# Audio-Module-SCH.net
KiCad netlist of a schematic drawn in Altium Designer
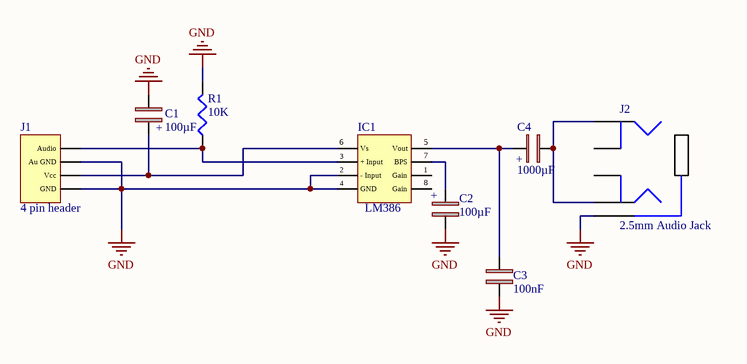
[diagram p0: Audio-Module-SCH.SchDoc]

(export (version "E")
  (design (tool "Eeschema 10.0.6"))
  (components
    (comp (ref "C1")
      (value "100µF")
      (footprint "ELCO")
      (description "CAP ALUM 100UF 20% 10V SMD")
      (fields
        (field (name "MANUFACTURER") "Panasonic")
        (field (name "MANUFACTURER PART NUMBER") "EEE-1AA101WR")
      )
      (libsource (lib "Audio-Module-SCH-LIB") (part "Capacitor{colon} 100µF (elco)"))
    )
    (comp (ref "C2")
      (value "100µF")
      (footprint "ELCO")
      (description "CAP ALUM 100UF 20% 10V SMD")
      (fields
        (field (name "MANUFACTURER") "Panasonic")
        (field (name "MANUFACTURER PART NUMBER") "EEE-1AA101WR")
      )
      (libsource (lib "") (part "Capacitor{colon} 100µF (elco)_1"))
    )
    (comp (ref "C3")
      (value "100nF")
      (footprint "CAPACITOR 1206")
      (description "Ceramic capacitor SMD-1206 100nF /50V X7R# K +-10%, AVX, RoHS, /4000 reel/")
      (fields
        (field (name "MANUFACTURER") "Kyocera AVX")
        (field (name "MANUFACTURER PART NUMBER") "12065C104KAT2A")
      )
      (libsource (lib "Audio-Module-SCH-LIB") (part "Capacitor{colon} 100nF"))
    )
    (comp (ref "C4")
      (value "1000µF")
      (footprint "ELCO")
      (description "Capacitor; Aluminum Electrolytic; Ecap 1000uF 25V H13 Case FK SMT")
      (fields
        (field (name "MANUFACTURER") "Panasonic")
        (field (name "MANUFACTURER PART NUMBER") "EEE-FK1E102AQ")
      )
      (libsource (lib "Audio-Module-SCH-LIB") (part "Capacitor{colon} 1000µF (elco)"))
    )
    (comp (ref "IC1")
      (value "LM386")
      (footprint "LM386 SOP8")
      (description "Audio Amplifier, 0.325W, 1 Chann")
      (fields
        (field (name "MANUFACTURER") "TI National Semiconductor")
        (field (name "MANUFACTURER PART NUMBER") "LM386M-1")
      )
      (libsource (lib "Audio-Module-SCH-LIB") (part "IC{colon} LM386"))
    )
    (comp (ref "J1")
      (value "4 pin header")
      (footprint "4 HDR")
      (description "Male 4 pin header")
      (libsource (lib "Audio-Module-SCH-LIB") (part "CONNECTOR{colon} 4 pin header"))
    )
    (comp (ref "J2")
      (value "2.5mm Audio Jack")
      (footprint "AUDIO JACK")
      (description "Conn Audio RCP 6 POS Solder RA SMD 6 Terminal 1 Port T/R")
      (fields
        (field (name "MANUFACTURER") "Kycon")
        (field (name "MANUFACTURER PART NUMBER") "STX-25427-6N-TR")
      )
      (libsource (lib "Audio-Module-SCH-LIB") (part "Connector{colon} Audio Jack"))
    )
    (comp (ref "R1")
      (value "10K")
      (footprint "RESISTOR 0805")
      (description "Res Thick Film 0805 10K Ohm 5% 1/8W ±200ppm/°C Molded SMD SMD Paper T/R")
      (fields
        (field (name "MANUFACTURER") "Vishay Dale")
        (field (name "MANUFACTURER PART NUMBER") "CRCW080510K0JNEB")
      )
      (libsource (lib "Audio-Module-SCH-LIB") (part "Resistor{colon} 10K R"))
    )
  )
  (nets
    (net (code "1") (name "GND") (class "Default")
      (node (ref "C1") (pin "2") (pinfunction "-_2") (pintype "passive"))
      (node (ref "C2") (pin "2") (pinfunction "-_2") (pintype "passive"))
      (node (ref "C3") (pin "2") (pinfunction "2_2") (pintype "passive"))
      (node (ref "IC1") (pin "2") (pinfunction "-_Input_2") (pintype "passive"))
      (node (ref "IC1") (pin "4") (pinfunction "GND_4") (pintype "passive"))
      (node (ref "J1") (pin "1") (pinfunction "GND_1") (pintype "passive"))
      (node (ref "J1") (pin "3") (pinfunction "Au_GND_3") (pintype "passive"))
      (node (ref "J2") (pin "5") (pinfunction "Sleeve_5") (pintype "passive"))
      (node (ref "R1") (pin "2") (pinfunction "2_2") (pintype "passive"))
    )
    (net (code "2") (name "Net-(C1-+)") (class "Default")
      (node (ref "C1") (pin "1") (pinfunction "+_1") (pintype "passive"))
      (node (ref "IC1") (pin "6") (pinfunction "Vs_6") (pintype "passive"))
      (node (ref "J1") (pin "2") (pinfunction "Vcc_2") (pintype "passive"))
    )
    (net (code "3") (name "Net-(C2-+)") (class "Default")
      (node (ref "C2") (pin "1") (pinfunction "+_1") (pintype "passive"))
      (node (ref "IC1") (pin "7") (pinfunction "BPS_7") (pintype "passive"))
    )
    (net (code "4") (name "Net-(C4-+)") (class "Default")
      (node (ref "C3") (pin "1") (pinfunction "1_1") (pintype "passive"))
      (node (ref "C4") (pin "1") (pinfunction "+_1") (pintype "passive"))
      (node (ref "IC1") (pin "5") (pinfunction "Vout_5") (pintype "passive"))
    )
    (net (code "5") (name "Net-(C4--)") (class "Default")
      (node (ref "C4") (pin "2") (pinfunction "-_2") (pintype "passive"))
      (node (ref "J2") (pin "1") (pinfunction "Ring_1") (pintype "passive"))
      (node (ref "J2") (pin "4") (pinfunction "Tip_4") (pintype "passive"))
    )
    (net (code "6") (name "Net-(IC1-+_Input)") (class "Default")
      (node (ref "IC1") (pin "3") (pinfunction "+_Input_3") (pintype "passive"))
      (node (ref "J1") (pin "4") (pinfunction "Audio_4") (pintype "passive"))
      (node (ref "R1") (pin "1") (pinfunction "1_1") (pintype "passive"))
    )
    (net (code "7") (name "unconnected-(IC1-Gain-Pad1)") (class "Default")
      (node (ref "IC1") (pin "1") (pinfunction "Gain_1") (pintype "passive"))
    )
    (net (code "8") (name "unconnected-(IC1-Gain-Pad8)") (class "Default")
      (node (ref "IC1") (pin "8") (pinfunction "Gain_8") (pintype "passive"))
    )
    (net (code "9") (name "unconnected-(J2-Ring_Switch-Pad2)") (class "Default")
      (node (ref "J2") (pin "2") (pinfunction "Ring_Switch_2") (pintype "passive"))
    )
    (net (code "10") (name "unconnected-(J2-Tip_Switch-Pad3)") (class "Default")
      (node (ref "J2") (pin "3") (pinfunction "Tip_Switch_3") (pintype "passive"))
    )
  )
)
